# ProPrj___2025-04-21.net
KiCad netlist of a schematic drawn in EasyEDA Pro
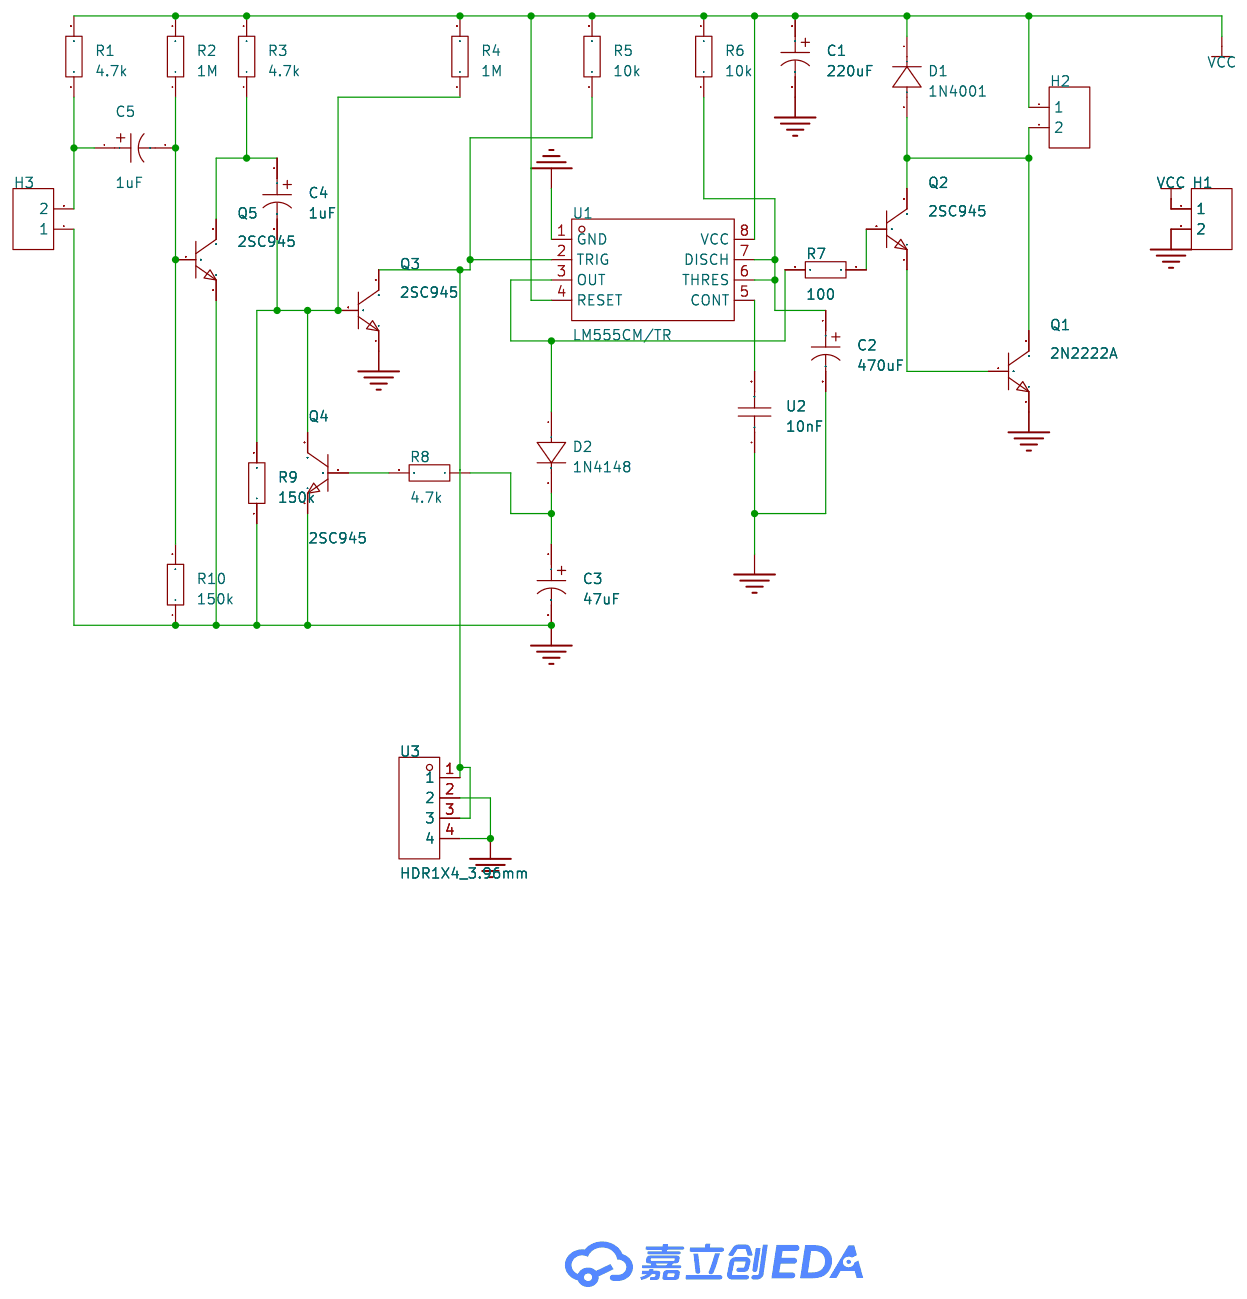
[diagram p0: schematic sheet]

(export (version "E")
  (design (tool "Eeschema 10.0.6"))
  (components
    (comp (ref "C1")
      (value "220uF")
      (footprint "easyedapro:CAP-TH_BD8.0-P3.50-D0.6-FD")
      (description "容值:220uF;精度:±20%;额定电压:25V;纹波电流:360mA@10kHz;等效串联电阻(ESR):-;")
      (fields
        (field (name "Manufacturer Part") "UKA1E221MPD1TD")
        (field (name "Manufacturer") "Nichicon(尼吉康)")
      )
      (libsource (lib "easyedapro") (part "UKA1E221MPD1TD"))
    )
    (comp (ref "C2")
      (value "470uF")
      (footprint "easyedapro:CAP-TH_BD8.0-P5.00-D0.6-FD")
      (description "容值:470uF;精度:±20%;额定电压:25V;纹波电流:-;等效串联电阻:-;")
      (fields
        (field (name "Manufacturer Part") "ERR1EM471F12P50")
        (field (name "Manufacturer") "AISHI(艾华集团)")
      )
      (libsource (lib "easyedapro") (part "ERR1EM471F12P50"))
    )
    (comp (ref "C3")
      (value "47uF")
      (footprint "easyedapro:CAP-TH_BD6.3-P2.50-D0.5-FD")
      (description "容值:47uF;精度:±20%;额定电压:63V;纹波电流:-;等效串联电阻(ESR):-;")
      (fields (field (name "Manufacturer Part") "CD26G1JM470E120T") (field (name "Manufacturer") "创慧电子"))
      (libsource (lib "easyedapro") (part "CD26G1JM470E120T"))
    )
    (comp (ref "C4")
      (value "1uF")
      (footprint "easyedapro:CAP-TH_BD6.3-P2.50-D0.5-FD")
      (description "容值:1uF;精度:±20%;额定电压:-;纹波电流:-;等效串联电阻:-;")
      (fields (field (name "Manufacturer Part") "UVR2E010MED") (field (name "Manufacturer") "Nichicon(尼吉康)"))
      (libsource (lib "easyedapro") (part "UVR2E010MED"))
    )
    (comp (ref "C5")
      (value "1uF")
      (footprint "easyedapro:CAP-TH_BD6.3-P2.50-D0.5-FD")
      (description "容值:1uF;精度:±20%;额定电压:-;纹波电流:-;等效串联电阻:-;")
      (fields (field (name "Manufacturer Part") "UVR2E010MED") (field (name "Manufacturer") "Nichicon(尼吉康)"))
      (libsource (lib "easyedapro") (part "UVR2E010MED"))
    )
    (comp (ref "D1")
      (value "1N4001")
      (footprint "easyedapro:SMA_L4.3-W2.6-LS5.1-RD")
      (libsource (lib "easyedapro") (part "1N4001_C9900008134"))
    )
    (comp (ref "D2")
      (value "1N4148")
      (footprint "easyedapro:DO-35_BD2.2-L4.0-D0.50_1N4148")
      (fields (field (name "Manufacturer") "LJ(朗捷)"))
      (libsource (lib "easyedapro") (part "1N4148_C18195411"))
    )
    (comp (ref "H1")
      (value "~")
      (footprint "easyedapro:HDR-TH_2P-P2.54-V-F")
      (libsource (lib "easyedapro") (part "Header-Female-2.54_1x2"))
    )
    (comp (ref "H2")
      (value "~")
      (footprint "easyedapro:HDR-TH_2P-P2.54-V-F")
      (libsource (lib "easyedapro") (part "Header-Female-2.54_1x2"))
    )
    (comp (ref "H3")
      (value "~")
      (footprint "easyedapro:HDR-TH_2P-P2.54-V-F")
      (libsource (lib "easyedapro") (part "Header-Female-2.54_1x2"))
    )
    (comp (ref "Q1")
      (value "2N2222A")
      (footprint "easyedapro:TO-92-3_L4.9-W3.7-P1.27-L")
      (description "晶体管类型:NPN;集电极电流(Ic):600mA;集射极击穿电压(Vceo):40V;功率(Pd):625mW;直流电流增益(hFE@Ic,Vce):40@500mA,10V;")
      (fields (field (name "Manufacturer") "ST(先科)"))
      (libsource (lib "easyedapro") (part "2N2222"))
    )
    (comp (ref "Q2")
      (value "2SC945")
      (footprint "easyedapro:TO-92-3_L4.9-W3.7-P1.27-L")
      (fields (field (name "Manufacturer") "ST(先科)"))
      (libsource (lib "easyedapro") (part "2SC945_C2987754"))
    )
    (comp (ref "Q3")
      (value "2SC945")
      (footprint "easyedapro:TO-92-3_L4.9-W3.7-P1.27-L")
      (fields (field (name "Manufacturer") "ST(先科)"))
      (libsource (lib "easyedapro") (part "2SC945_C2987754"))
    )
    (comp (ref "Q4")
      (value "2SC945")
      (footprint "easyedapro:TO-92-3_L4.9-W3.7-P1.27-L")
      (fields (field (name "Manufacturer") "ST(先科)"))
      (libsource (lib "easyedapro") (part "2SC945_C2987754"))
    )
    (comp (ref "Q5")
      (value "2SC945")
      (footprint "easyedapro:TO-92-3_L4.9-W3.7-P1.27-L")
      (fields (field (name "Manufacturer") "ST(先科)"))
      (libsource (lib "easyedapro") (part "2SC945_C2987754"))
    )
    (comp (ref "R1") (value "4.7k") (footprint "easyedapro:R0603") (libsource (lib "easyedapro") (part "电阻")))
    (comp (ref "R2") (value "1M") (footprint "easyedapro:R0603") (libsource (lib "easyedapro") (part "电阻")))
    (comp (ref "R3") (value "4.7k") (footprint "easyedapro:R0603") (libsource (lib "easyedapro") (part "电阻")))
    (comp (ref "R4") (value "1M") (footprint "easyedapro:R0603") (libsource (lib "easyedapro") (part "电阻")))
    (comp (ref "R5") (value "10k") (footprint "easyedapro:R0603") (libsource (lib "easyedapro") (part "电阻")))
    (comp (ref "R6") (value "10k") (footprint "easyedapro:R0603") (libsource (lib "easyedapro") (part "电阻")))
    (comp (ref "R7") (value "100") (footprint "easyedapro:R0603") (libsource (lib "easyedapro") (part "电阻")))
    (comp (ref "R8") (value "4.7k") (footprint "easyedapro:R0603") (libsource (lib "easyedapro") (part "电阻")))
    (comp (ref "R9") (value "150k") (footprint "easyedapro:R0603") (libsource (lib "easyedapro") (part "电阻")))
    (comp (ref "R10")
      (value "150k")
      (footprint "easyedapro:R0603")
      (libsource (lib "easyedapro") (part "电阻"))
    )
    (comp (ref "U1")
      (value "LM555CM/TR")
      (footprint "easyedapro:SOP-8_L4.9-W3.9-P1.27-LS6.0-BL-1")
      (description "定时器/计时器/时钟振荡器  高精度定时脉冲的双极性集成电路")
      (fields (field (name "Manufacturer") "HGSEMI(华冠)"))
      (libsource (lib "easyedapro") (part "LM555CM/TR"))
    )
    (comp (ref "U2")
      (value "10nF")
      (footprint "easyedapro:C1206")
      (libsource (lib "easyedapro") (part "10NF"))
    )
    (comp (ref "U3")
      (value "HDR1X4_3.96mm")
      (footprint "easyedapro:CONN-TH_4P-P3.96_FWF39601-S04S22W1B")
      (libsource (lib "easyedapro") (part "HDR1X4_3.96MM"))
    )
  )
  (nets
    (net (code "1") (name "GND") (class "Default")
      (node (ref "C1") (pin "2") (pinfunction "2_2") (pintype "input"))
      (node (ref "C2") (pin "2") (pinfunction "2_2") (pintype "input"))
      (node (ref "C3") (pin "2") (pinfunction "2_2") (pintype "input"))
      (node (ref "H1") (pin "2") (pinfunction "2_2") (pintype "input"))
      (node (ref "H3") (pin "1") (pinfunction "1_1") (pintype "input"))
      (node (ref "Q1") (pin "1") (pinfunction "E_1") (pintype "unspecified"))
      (node (ref "Q3") (pin "1") (pinfunction "E_1") (pintype "unspecified"))
      (node (ref "Q4") (pin "1") (pinfunction "E_1") (pintype "unspecified"))
      (node (ref "Q5") (pin "1") (pinfunction "E_1") (pintype "unspecified"))
      (node (ref "R10") (pin "1") (pinfunction "1_1") (pintype "input"))
      (node (ref "R9") (pin "1") (pinfunction "1_1") (pintype "input"))
      (node (ref "U1") (pin "1") (pinfunction "GND_1") (pintype "unspecified"))
      (node (ref "U2") (pin "1") (pinfunction "1_1") (pintype "unspecified"))
      (node (ref "U3") (pin "2") (pinfunction "2_2") (pintype "unspecified"))
      (node (ref "U3") (pin "4") (pinfunction "4_4") (pintype "unspecified"))
    )
    (net (code "2") (name "Net-(C5-Pad1)") (class "Default")
      (node (ref "C5") (pin "1") (pinfunction "1_1") (pintype "input"))
      (node (ref "H3") (pin "2") (pinfunction "2_2") (pintype "input"))
      (node (ref "R1") (pin "1") (pinfunction "1_1") (pintype "input"))
    )
    (net (code "3") (name "Net-(D1-A)") (class "Default")
      (node (ref "D1") (pin "2") (pinfunction "A_2") (pintype "unspecified"))
      (node (ref "H2") (pin "2") (pinfunction "2_2") (pintype "input"))
      (node (ref "Q1") (pin "3") (pinfunction "C_3") (pintype "unspecified"))
      (node (ref "Q2") (pin "2") (pinfunction "C_2") (pintype "unspecified"))
    )
    (net (code "4") (name "Net-(D2-A)") (class "Default")
      (node (ref "D2") (pin "1") (pinfunction "A_1") (pintype "unspecified"))
      (node (ref "R7") (pin "2") (pinfunction "2_2") (pintype "input"))
      (node (ref "U1") (pin "3") (pinfunction "OUT_3") (pintype "unspecified"))
    )
    (net (code "5") (name "Net-(D2-C)") (class "Default")
      (node (ref "C3") (pin "1") (pinfunction "1_1") (pintype "input"))
      (node (ref "D2") (pin "2") (pinfunction "C_2") (pintype "unspecified"))
      (node (ref "R8") (pin "1") (pinfunction "1_1") (pintype "input"))
    )
    (net (code "6") (name "Net-(Q1-B)") (class "Default")
      (node (ref "Q1") (pin "2") (pinfunction "B_2") (pintype "unspecified"))
      (node (ref "Q2") (pin "1") (pinfunction "E_1") (pintype "unspecified"))
    )
    (net (code "7") (name "Net-(Q2-B)") (class "Default")
      (node (ref "Q2") (pin "3") (pinfunction "B_3") (pintype "unspecified"))
      (node (ref "R7") (pin "1") (pinfunction "1_1") (pintype "input"))
    )
    (net (code "8") (name "Net-(Q3-B)") (class "Default")
      (node (ref "C4") (pin "2") (pinfunction "2_2") (pintype "input"))
      (node (ref "Q3") (pin "3") (pinfunction "B_3") (pintype "unspecified"))
      (node (ref "Q4") (pin "2") (pinfunction "C_2") (pintype "unspecified"))
      (node (ref "R4") (pin "1") (pinfunction "1_1") (pintype "input"))
      (node (ref "R9") (pin "2") (pinfunction "2_2") (pintype "input"))
    )
    (net (code "9") (name "Net-(Q3-C)") (class "Default")
      (node (ref "Q3") (pin "2") (pinfunction "C_2") (pintype "unspecified"))
      (node (ref "R5") (pin "1") (pinfunction "1_1") (pintype "input"))
      (node (ref "U1") (pin "2") (pinfunction "TRIG_2") (pintype "unspecified"))
      (node (ref "U3") (pin "1") (pinfunction "1_1") (pintype "unspecified"))
      (node (ref "U3") (pin "3") (pinfunction "3_3") (pintype "unspecified"))
    )
    (net (code "10") (name "Net-(Q4-B)") (class "Default")
      (node (ref "Q4") (pin "3") (pinfunction "B_3") (pintype "unspecified"))
      (node (ref "R8") (pin "2") (pinfunction "2_2") (pintype "input"))
    )
    (net (code "11") (name "Net-(Q5-B)") (class "Default")
      (node (ref "C5") (pin "2") (pinfunction "2_2") (pintype "input"))
      (node (ref "Q5") (pin "3") (pinfunction "B_3") (pintype "unspecified"))
      (node (ref "R10") (pin "2") (pinfunction "2_2") (pintype "input"))
      (node (ref "R2") (pin "1") (pinfunction "1_1") (pintype "input"))
    )
    (net (code "12") (name "Net-(Q5-C)") (class "Default")
      (node (ref "C4") (pin "1") (pinfunction "1_1") (pintype "input"))
      (node (ref "Q5") (pin "2") (pinfunction "C_2") (pintype "unspecified"))
      (node (ref "R3") (pin "1") (pinfunction "1_1") (pintype "input"))
    )
    (net (code "13") (name "Net-(U1-CONT)") (class "Default")
      (node (ref "U1") (pin "5") (pinfunction "CONT_5") (pintype "unspecified"))
      (node (ref "U2") (pin "2") (pinfunction "2_2") (pintype "unspecified"))
    )
    (net (code "14") (name "Net-(U1-DISCH)") (class "Default")
      (node (ref "C2") (pin "1") (pinfunction "1_1") (pintype "input"))
      (node (ref "R6") (pin "1") (pinfunction "1_1") (pintype "input"))
      (node (ref "U1") (pin "6") (pinfunction "THRES_6") (pintype "unspecified"))
      (node (ref "U1") (pin "7") (pinfunction "DISCH_7") (pintype "unspecified"))
    )
    (net (code "15") (name "VCC") (class "Default")
      (node (ref "C1") (pin "1") (pinfunction "1_1") (pintype "input"))
      (node (ref "D1") (pin "1") (pinfunction "K_1") (pintype "unspecified"))
      (node (ref "H1") (pin "1") (pinfunction "1_1") (pintype "input"))
      (node (ref "H2") (pin "1") (pinfunction "1_1") (pintype "input"))
      (node (ref "R1") (pin "2") (pinfunction "2_2") (pintype "input"))
      (node (ref "R2") (pin "2") (pinfunction "2_2") (pintype "input"))
      (node (ref "R3") (pin "2") (pinfunction "2_2") (pintype "input"))
      (node (ref "R4") (pin "2") (pinfunction "2_2") (pintype "input"))
      (node (ref "R5") (pin "2") (pinfunction "2_2") (pintype "input"))
      (node (ref "R6") (pin "2") (pinfunction "2_2") (pintype "input"))
      (node (ref "U1") (pin "4") (pinfunction "RESET_4") (pintype "unspecified"))
      (node (ref "U1") (pin "8") (pinfunction "VCC_8") (pintype "unspecified"))
    )
  )
)
